# Carte_IPAv.net
KiCad netlist of a schematic drawn in Altium Designer
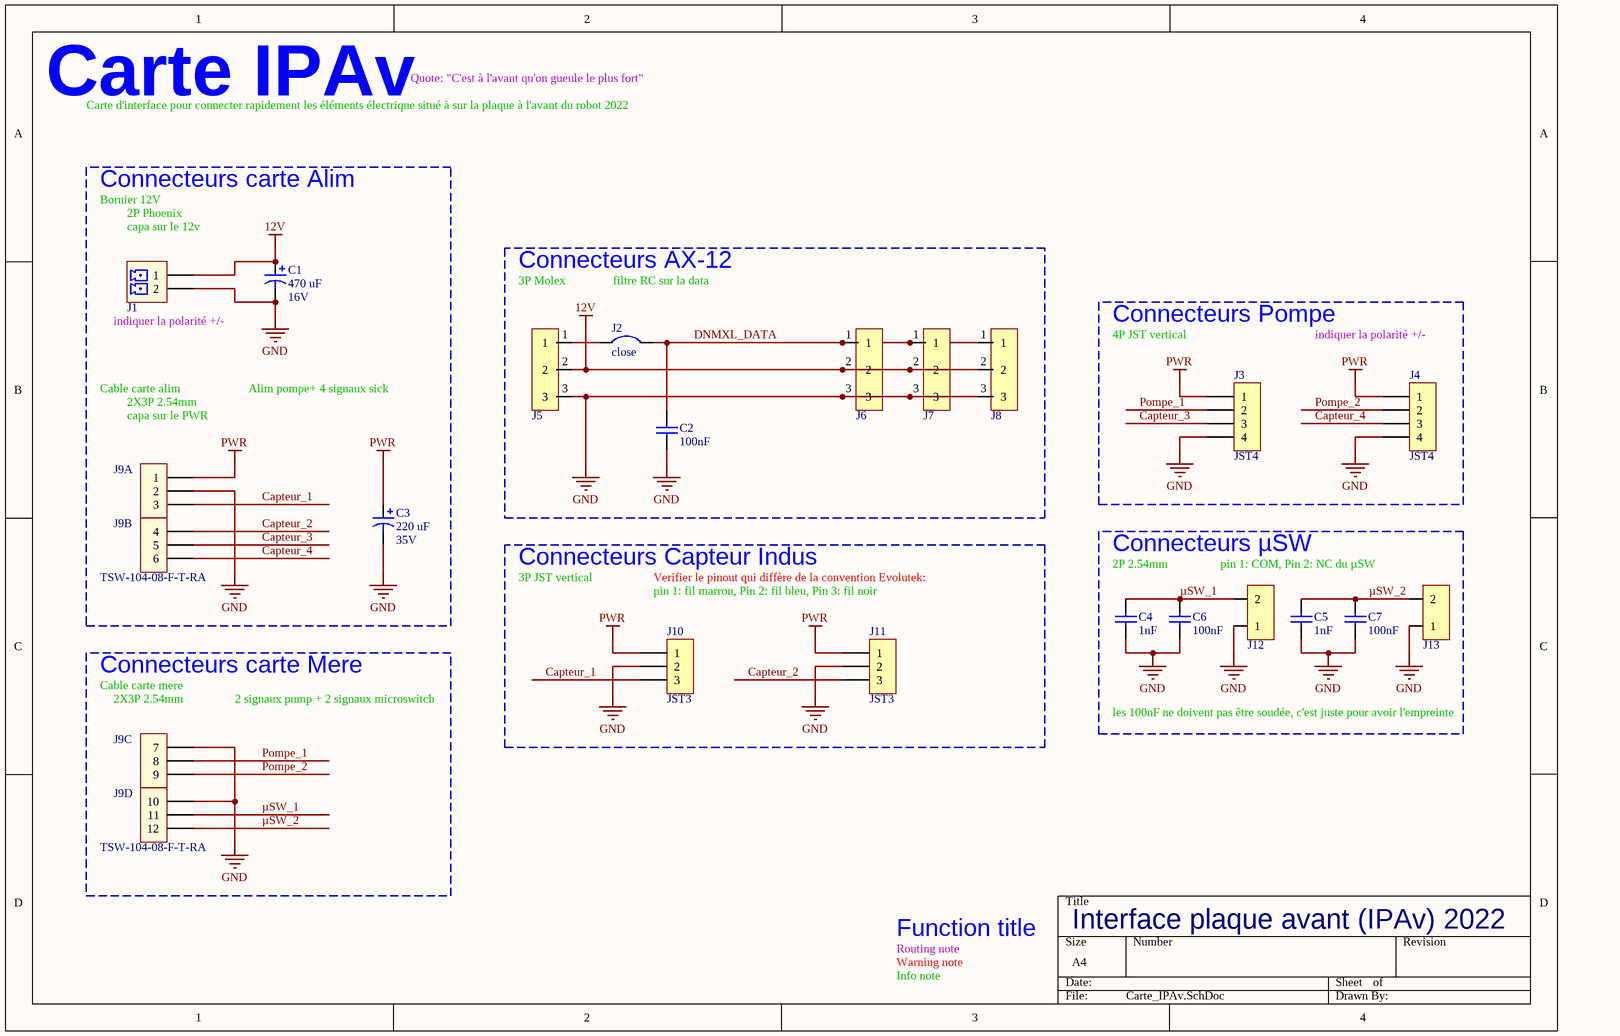
[diagram p0: Carte_IPAv.SchDoc]

(export (version "E")
  (design (tool "Eeschema 10.0.6"))
  (components
    (comp (ref "C1")
      (value "470 uF")
      (footprint "WCAP-ATG8_8x11.5x3.5x0.5")
      (description "CAP Alu 470 UF 20% 16 V")
      (fields
        (field (name "MANUFACTURER") "Wurth Elektronik")
        (field (name "MANUFACTURER PART NUMBER") "860010374012")
        (field (name "RATEDVOLTAGE") "16V")
      )
      (libsource (lib "Condensateur") (part "WCAP-ATG8, 860010374012"))
    )
    (comp (ref "C2")
      (value "100nF")
      (footprint "WCAP-CSGP_0603, 1.6x0.8x0.8")
      (description "CAP CER 100nF 50V X7R 0603")
      (fields
        (field (name "MANUFACTURER") "Wurth Elektronik")
        (field (name "MANUFACTURER PART NUMBER") "885012206095")
      )
      (libsource (lib "Condensateur") (part "WCAP-CSGP, 885012206095"))
    )
    (comp (ref "C3")
      (value "220 uF")
      (footprint "WCAP-ATG8_8x11.5x3.5x0.5")
      (description "CAP Alu 220 UF 20% 35 V")
      (fields
        (field (name "MANUFACTURER") "Wurth Elektronik")
        (field (name "MANUFACTURER PART NUMBER") "860010574011")
        (field (name "RATEDVOLTAGE") "35V")
      )
      (libsource (lib "Condensateur") (part "WCAP-ATG8, 860010574011"))
    )
    (comp (ref "C4")
      (value "1nF")
      (footprint "WCAP-CSGP_0402, 1x0.5x0.5")
      (description "CAP CER 1nF 50V X7R 0402")
      (fields
        (field (name "MANUFACTURER") "Wurth Elektronik")
        (field (name "MANUFACTURER PART NUMBER") "885012205061")
      )
      (libsource (lib "Condensateur") (part "WCAP-CSGP, 885012205061"))
    )
    (comp (ref "C5")
      (value "1nF")
      (footprint "WCAP-CSGP_0402, 1x0.5x0.5")
      (description "CAP CER 1nF 50V X7R 0402")
      (fields
        (field (name "MANUFACTURER") "Wurth Elektronik")
        (field (name "MANUFACTURER PART NUMBER") "885012205061")
      )
      (libsource (lib "Condensateur") (part "WCAP-CSGP, 885012205061"))
    )
    (comp (ref "C6")
      (value "100nF")
      (footprint "WCAP-CSGP_0603, 1.6x0.8x0.8")
      (description "CAP CER 100nF 50V X7R 0603")
      (fields
        (field (name "MANUFACTURER") "Wurth Elektronik")
        (field (name "MANUFACTURER PART NUMBER") "885012206095")
      )
      (libsource (lib "Condensateur") (part "WCAP-CSGP, 885012206095"))
    )
    (comp (ref "C7")
      (value "100nF")
      (footprint "WCAP-CSGP_0603, 1.6x0.8x0.8")
      (description "CAP CER 100nF 50V X7R 0603")
      (fields
        (field (name "MANUFACTURER") "Wurth Elektronik")
        (field (name "MANUFACTURER PART NUMBER") "885012206095")
      )
      (libsource (lib "Condensateur") (part "WCAP-CSGP, 885012206095"))
    )
    (comp (ref "J1")
      (value "691322110002")
      (footprint "691322110002")
      (description "WR-TBL 2p Series 3221 - 3.50 mm Horizontal PCB Header")
      (fields (field (name "MANUFACTURER") "Wurth Electronics Inc."))
      (libsource (lib "Connecteurs") (part "691322110002"))
    )
    (comp (ref "J2")
      (value "close")
      (footprint "CAVALIER_0603_C")
      (description "Cavalier soudure \"fermé\" + empreinte dipole 0603")
      (libsource (lib "Divers") (part "CAVALIER_0603_C"))
    )
    (comp (ref "J3") (value "JST4") (footprint "JST4") (libsource (lib "JST") (part "JST4")))
    (comp (ref "J4") (value "JST4") (footprint "JST4") (libsource (lib "JST") (part "JST4")))
    (comp (ref "J5")
      (value "22-03-5035")
      (footprint "20-03-5035")
      (description "CONN HEADER VERT 3POS 2.5MM")
      (fields (field (name "MANUFACTURER") "MOLEX"))
      (libsource (lib "") (part "20-03-5035_1"))
    )
    (comp (ref "J6")
      (value "22-03-5035")
      (footprint "20-03-5035")
      (description "CONN HEADER VERT 3POS 2.5MM")
      (fields (field (name "MANUFACTURER") "MOLEX"))
      (libsource (lib "Connecteurs") (part "20-03-5035"))
    )
    (comp (ref "J7")
      (value "22-03-5035")
      (footprint "20-03-5035")
      (description "CONN HEADER VERT 3POS 2.5MM")
      (fields (field (name "MANUFACTURER") "MOLEX"))
      (libsource (lib "Connecteurs") (part "20-03-5035"))
    )
    (comp (ref "J8")
      (value "22-03-5035")
      (footprint "20-03-5035")
      (description "CONN HEADER VERT 3POS 2.5MM")
      (fields (field (name "MANUFACTURER") "MOLEX"))
      (libsource (lib "Connecteurs") (part "20-03-5035"))
    )
    (comp (ref "J9")
      (value "TSW-104-08-F-T-RA")
      (footprint "TSW-104-08-F-T-RA")
      (description "CONN HEADER R/A 3L x 4POS 2.54MM")
      (fields (field (name "MANUFACTURER") "SAMTEC"))
      (libsource (lib "Connecteurs") (part "TSW-104-08-F-T-RA"))
    )
    (comp (ref "J10") (value "JST3") (footprint "JST3") (libsource (lib "JST") (part "JST3")))
    (comp (ref "J11") (value "JST3") (footprint "JST3") (libsource (lib "JST") (part "JST3")))
    (comp (ref "J12")
      (value "22-03-2021")
      (footprint "22-03-2021")
      (description "CONN HEADER VERT 2POS 2.54MM")
      (fields (field (name "MANUFACTURER") "MOLEX"))
      (libsource (lib "Molex") (part "22-03-2021"))
    )
    (comp (ref "J13")
      (value "22-03-2021")
      (footprint "22-03-2021")
      (description "CONN HEADER VERT 2POS 2.54MM")
      (fields (field (name "MANUFACTURER") "MOLEX"))
      (libsource (lib "Molex") (part "22-03-2021"))
    )
  )
  (nets
    (net (code "1") (name "/Capteur_1") (class "Default")
      (node (ref "J10") (pin "3") (pinfunction "3_3") (pintype "passive"))
      (node (ref "J9") (pin "3") (pinfunction "3_3") (pintype "passive"))
    )
    (net (code "2") (name "/Capteur_2") (class "Default")
      (node (ref "J11") (pin "3") (pinfunction "3_3") (pintype "passive"))
      (node (ref "J9") (pin "4") (pinfunction "4_4") (pintype "passive"))
    )
    (net (code "3") (name "/Capteur_3") (class "Default")
      (node (ref "J3") (pin "3") (pinfunction "3_3") (pintype "passive"))
      (node (ref "J9") (pin "5") (pinfunction "5_5") (pintype "passive"))
    )
    (net (code "4") (name "/Capteur_4") (class "Default")
      (node (ref "J4") (pin "3") (pinfunction "3_3") (pintype "passive"))
      (node (ref "J9") (pin "6") (pinfunction "6_6") (pintype "passive"))
    )
    (net (code "5") (name "/DNMXL_DATA") (class "Default")
      (node (ref "C2") (pin "1") (pinfunction "1_1") (pintype "passive"))
      (node (ref "J2") (pin "2") (pinfunction "2_2") (pintype "passive"))
      (node (ref "J6") (pin "1") (pinfunction "1_1") (pintype "passive"))
      (node (ref "J7") (pin "1") (pinfunction "1_1") (pintype "passive"))
      (node (ref "J8") (pin "1") (pinfunction "1_1") (pintype "passive"))
    )
    (net (code "6") (name "/Pompe_1") (class "Default")
      (node (ref "J3") (pin "2") (pinfunction "2_2") (pintype "passive"))
      (node (ref "J9") (pin "8") (pinfunction "8_8") (pintype "passive"))
    )
    (net (code "7") (name "/Pompe_2") (class "Default")
      (node (ref "J4") (pin "2") (pinfunction "2_2") (pintype "passive"))
      (node (ref "J9") (pin "9") (pinfunction "9_9") (pintype "passive"))
    )
    (net (code "8") (name "/µSW_1") (class "Default")
      (node (ref "C4") (pin "1") (pinfunction "1_1") (pintype "passive"))
      (node (ref "C6") (pin "1") (pinfunction "1_1") (pintype "passive"))
      (node (ref "J12") (pin "2") (pinfunction "2_2") (pintype "passive"))
      (node (ref "J9") (pin "11") (pinfunction "11_11") (pintype "passive"))
    )
    (net (code "9") (name "/µSW_2") (class "Default")
      (node (ref "C5") (pin "1") (pinfunction "1_1") (pintype "passive"))
      (node (ref "C7") (pin "1") (pinfunction "1_1") (pintype "passive"))
      (node (ref "J13") (pin "2") (pinfunction "2_2") (pintype "passive"))
      (node (ref "J9") (pin "12") (pinfunction "12_12") (pintype "passive"))
    )
    (net (code "10") (name "12V") (class "Default")
      (node (ref "C1") (pin "1") (pinfunction "1_1") (pintype "passive"))
      (node (ref "J1") (pin "1") (pinfunction "1_1") (pintype "passive"))
      (node (ref "J5") (pin "2") (pinfunction "2_2") (pintype "passive"))
      (node (ref "J6") (pin "2") (pinfunction "2_2") (pintype "passive"))
      (node (ref "J7") (pin "2") (pinfunction "2_2") (pintype "passive"))
      (node (ref "J8") (pin "2") (pinfunction "2_2") (pintype "passive"))
    )
    (net (code "11") (name "GND") (class "Default")
      (node (ref "C1") (pin "2") (pinfunction "2_2") (pintype "passive"))
      (node (ref "C2") (pin "2") (pinfunction "2_2") (pintype "passive"))
      (node (ref "C3") (pin "2") (pinfunction "2_2") (pintype "passive"))
      (node (ref "C4") (pin "2") (pinfunction "2_2") (pintype "passive"))
      (node (ref "C5") (pin "2") (pinfunction "2_2") (pintype "passive"))
      (node (ref "C6") (pin "2") (pinfunction "2_2") (pintype "passive"))
      (node (ref "C7") (pin "2") (pinfunction "2_2") (pintype "passive"))
      (node (ref "J1") (pin "2") (pinfunction "2_2") (pintype "passive"))
      (node (ref "J10") (pin "2") (pinfunction "2_2") (pintype "passive"))
      (node (ref "J11") (pin "2") (pinfunction "2_2") (pintype "passive"))
      (node (ref "J12") (pin "1") (pinfunction "1_1") (pintype "passive"))
      (node (ref "J13") (pin "1") (pinfunction "1_1") (pintype "passive"))
      (node (ref "J3") (pin "4") (pinfunction "4_4") (pintype "passive"))
      (node (ref "J4") (pin "4") (pinfunction "4_4") (pintype "passive"))
      (node (ref "J5") (pin "3") (pinfunction "3_3") (pintype "passive"))
      (node (ref "J6") (pin "3") (pinfunction "3_3") (pintype "passive"))
      (node (ref "J7") (pin "3") (pinfunction "3_3") (pintype "passive"))
      (node (ref "J8") (pin "3") (pinfunction "3_3") (pintype "passive"))
      (node (ref "J9") (pin "10") (pinfunction "10_10") (pintype "passive"))
      (node (ref "J9") (pin "2") (pinfunction "2_2") (pintype "passive"))
      (node (ref "J9") (pin "7") (pinfunction "7_7") (pintype "passive"))
    )
    (net (code "12") (name "Net-(J2-Pad1)") (class "Default")
      (node (ref "J2") (pin "1") (pinfunction "1_1") (pintype "passive"))
      (node (ref "J5") (pin "1") (pinfunction "1_1") (pintype "passive"))
    )
    (net (code "13") (name "PWR") (class "Default")
      (node (ref "C3") (pin "1") (pinfunction "1_1") (pintype "passive"))
      (node (ref "J10") (pin "1") (pinfunction "1_1") (pintype "passive"))
      (node (ref "J11") (pin "1") (pinfunction "1_1") (pintype "passive"))
      (node (ref "J3") (pin "1") (pinfunction "1_1") (pintype "passive"))
      (node (ref "J4") (pin "1") (pinfunction "1_1") (pintype "passive"))
      (node (ref "J9") (pin "1") (pinfunction "1_1") (pintype "passive"))
    )
  )
)
